# 304_usb_serial020000.net
KiCad netlist of a schematic drawn in EAGLE
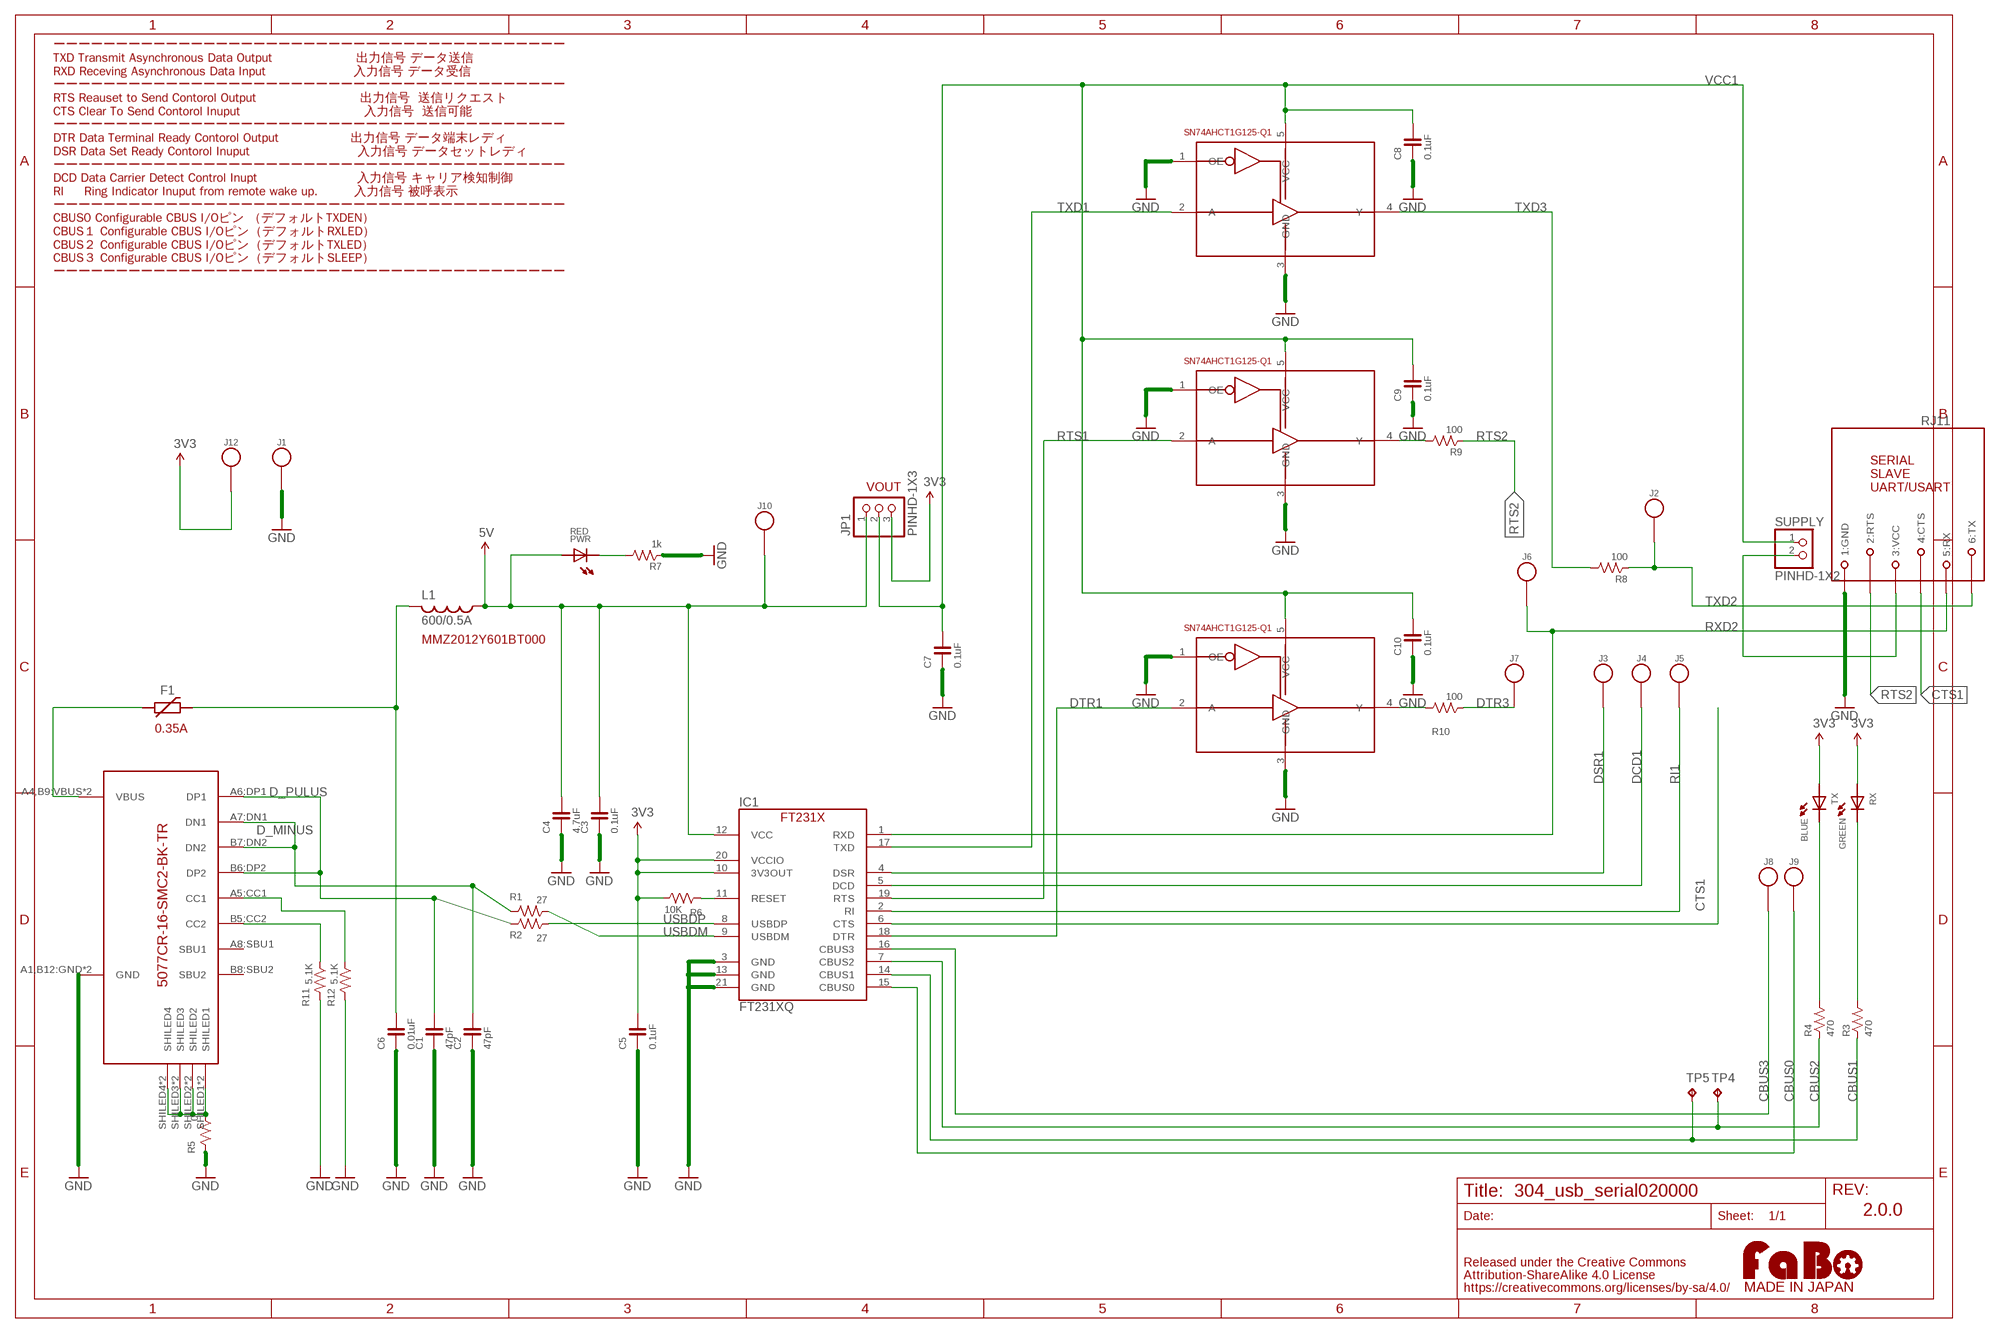
[diagram p0: schematic, sheet 1]

(export (version "E")
  (design (tool "Eeschema 10.0.6"))
  (components
    (comp (ref "C1")
      (value "47pF")
      (footprint "eagle-import:0603-NARROW")
      (libsource (lib "eagle-import") (part "CAPACITOR-0603_NARROW"))
    )
    (comp (ref "C2")
      (value "47pF")
      (footprint "eagle-import:0603-NARROW")
      (libsource (lib "eagle-import") (part "CAPACITOR-0603_NARROW"))
    )
    (comp (ref "C3")
      (value "0.1uF")
      (footprint "eagle-import:0603-NARROW")
      (libsource (lib "eagle-import") (part "CAPACITOR-0603_NARROW"))
    )
    (comp (ref "C4")
      (value "4.7uF")
      (footprint "eagle-import:0603-NARROW")
      (libsource (lib "eagle-import") (part "CAPACITOR-0603_NARROW"))
    )
    (comp (ref "C5")
      (value "0.1uF")
      (footprint "eagle-import:0603-NARROW")
      (libsource (lib "eagle-import") (part "CAPACITOR-0603_NARROW"))
    )
    (comp (ref "C6")
      (value "0.01uF")
      (footprint "eagle-import:0603-NARROW")
      (libsource (lib "eagle-import") (part "CAPACITOR-0603_NARROW"))
    )
    (comp (ref "C7")
      (value "0.1uF")
      (footprint "eagle-import:0603-NARROW")
      (libsource (lib "eagle-import") (part "CAPACITOR-0603_NARROW"))
    )
    (comp (ref "C8")
      (value "0.1uF")
      (footprint "eagle-import:0402-NO_SILK")
      (libsource (lib "eagle-import") (part "CAPACITOR-0402-NO_SILK"))
    )
    (comp (ref "C9")
      (value "0.1uF")
      (footprint "eagle-import:0402-NO_SILK")
      (libsource (lib "eagle-import") (part "CAPACITOR-0402-NO_SILK"))
    )
    (comp (ref "C10")
      (value "0.1uF")
      (footprint "eagle-import:0402-NO_SILK")
      (libsource (lib "eagle-import") (part "CAPACITOR-0402-NO_SILK"))
    )
    (comp (ref "F1")
      (value "350mA")
      (footprint "eagle-import:NANOSMDC035F")
      (libsource (lib "eagle-import") (part "POLYSWITCH"))
    )
    (comp (ref "IC1")
      (value "FT231XQ")
      (footprint "eagle-import:QFN-20_FT231X")
      (libsource (lib "eagle-import") (part "FT231XQ"))
    )
    (comp (ref "J1")
      (value "PIN_HEADER_1X1_NOLABEL_C")
      (footprint "eagle-import:PIN_1X1_NOLABEL")
      (libsource (lib "eagle-import") (part "PIN_HEADER_1X1_NOLABEL_C"))
    )
    (comp (ref "J2")
      (value "PIN_HEADER_1X1_NOLABEL_C")
      (footprint "eagle-import:PIN_1X1_NOLABEL")
      (libsource (lib "eagle-import") (part "PIN_HEADER_1X1_NOLABEL_C"))
    )
    (comp (ref "J3")
      (value "PIN_HEADER_1X1_NOLABEL_C")
      (footprint "eagle-import:PIN_1X1_NOLABEL")
      (libsource (lib "eagle-import") (part "PIN_HEADER_1X1_NOLABEL_C"))
    )
    (comp (ref "J4")
      (value "PIN_HEADER_1X1_NOLABEL_C")
      (footprint "eagle-import:PIN_1X1_NOLABEL")
      (libsource (lib "eagle-import") (part "PIN_HEADER_1X1_NOLABEL_C"))
    )
    (comp (ref "J5")
      (value "PIN_HEADER_1X1_NOLABEL_C")
      (footprint "eagle-import:PIN_1X1_NOLABEL")
      (libsource (lib "eagle-import") (part "PIN_HEADER_1X1_NOLABEL_C"))
    )
    (comp (ref "J6")
      (value "PIN_HEADER_1X1_NOLABEL_C")
      (footprint "eagle-import:PIN_1X1_NOLABEL")
      (libsource (lib "eagle-import") (part "PIN_HEADER_1X1_NOLABEL_C"))
    )
    (comp (ref "J7")
      (value "PIN_HEADER_1X1_NOLABEL_C")
      (footprint "eagle-import:PIN_1X1_NOLABEL")
      (libsource (lib "eagle-import") (part "PIN_HEADER_1X1_NOLABEL_C"))
    )
    (comp (ref "J8")
      (value "PIN_HEADER_1X1_NOLABEL_C")
      (footprint "eagle-import:PIN_1X1_NOLABEL")
      (libsource (lib "eagle-import") (part "PIN_HEADER_1X1_NOLABEL_C"))
    )
    (comp (ref "J9")
      (value "PIN_HEADER_1X1_NOLABEL_C")
      (footprint "eagle-import:PIN_1X1_NOLABEL")
      (libsource (lib "eagle-import") (part "PIN_HEADER_1X1_NOLABEL_C"))
    )
    (comp (ref "J10")
      (value "PIN_HEADER_1X1_NOLABEL_C")
      (footprint "eagle-import:PIN_1X1_NOLABEL")
      (libsource (lib "eagle-import") (part "PIN_HEADER_1X1_NOLABEL_C"))
    )
    (comp (ref "J12")
      (value "PIN_HEADER_1X1_NOLABEL_C")
      (footprint "eagle-import:PIN_1X1_NOLABEL")
      (libsource (lib "eagle-import") (part "PIN_HEADER_1X1_NOLABEL_C"))
    )
    (comp (ref "JP1")
      (value "PINHD-1X3")
      (footprint "eagle-import:1X03")
      (libsource (lib "eagle-import") (part "PINHD-1X3"))
    )
    (comp (ref "L1")
      (value "600/0.5A")
      (footprint "eagle-import:RESC0805_L")
      (libsource (lib "eagle-import") (part "INDUCTOR_0805_L"))
    )
    (comp (ref "PWR")
      (value "RED")
      (footprint "eagle-import:0603-NARROW")
      (libsource (lib "eagle-import") (part "LED-0603-NARROW"))
    )
    (comp (ref "R1")
      (value "27")
      (footprint "eagle-import:0603-NARROW")
      (libsource (lib "eagle-import") (part "RESISTOR-0603-NARROW"))
    )
    (comp (ref "R2")
      (value "27")
      (footprint "eagle-import:0603-NARROW")
      (libsource (lib "eagle-import") (part "RESISTOR-0603-NARROW"))
    )
    (comp (ref "R3")
      (value "470")
      (footprint "eagle-import:0603-NARROW")
      (libsource (lib "eagle-import") (part "RESISTOR-0603-NARROW"))
    )
    (comp (ref "R4")
      (value "470")
      (footprint "eagle-import:0603-NARROW")
      (libsource (lib "eagle-import") (part "RESISTOR-0603-NARROW"))
    )
    (comp (ref "R5")
      (value "0")
      (footprint "eagle-import:0603-NARROW")
      (libsource (lib "eagle-import") (part "RESISTOR-0603-NARROW"))
    )
    (comp (ref "R6")
      (value "10K")
      (footprint "eagle-import:0603-NARROW")
      (libsource (lib "eagle-import") (part "RESISTOR-0603-NARROW"))
    )
    (comp (ref "R7")
      (value "1k")
      (footprint "eagle-import:0603-NARROW")
      (libsource (lib "eagle-import") (part "RESISTOR-0603-NARROW"))
    )
    (comp (ref "R8")
      (value "100")
      (footprint "eagle-import:0603-NARROW")
      (libsource (lib "eagle-import") (part "RESISTOR-0603-NARROW"))
    )
    (comp (ref "R9")
      (value "100")
      (footprint "eagle-import:0603-NARROW")
      (libsource (lib "eagle-import") (part "RESISTOR-0603-NARROW"))
    )
    (comp (ref "R10")
      (value "100")
      (footprint "eagle-import:0603-NARROW")
      (libsource (lib "eagle-import") (part "RESISTOR-0603-NARROW"))
    )
    (comp (ref "R11")
      (value "5.1K")
      (footprint "eagle-import:0603-NARROW")
      (libsource (lib "eagle-import") (part "RESISTOR-0603-NARROW"))
    )
    (comp (ref "R12")
      (value "5.1K")
      (footprint "eagle-import:0603-NARROW")
      (libsource (lib "eagle-import") (part "RESISTOR-0603-NARROW"))
    )
    (comp (ref "RJ11")
      (value "MODULAR-JACK-6P-RJ11_SERIAL_S_USART")
      (footprint "eagle-import:7002-6PXC-X")
      (libsource (lib "eagle-import") (part "MODULAR-JACK-6P-RJ11_SERIAL_S_USART"))
    )
    (comp (ref "RX")
      (value "GREEN")
      (footprint "eagle-import:0603-NARROW")
      (libsource (lib "eagle-import") (part "LED-0603-NARROW"))
    )
    (comp (ref "SUPPLY")
      (value "PINHD-1X2")
      (footprint "eagle-import:1X02")
      (libsource (lib "eagle-import") (part "PINHD-1X2"))
    )
    (comp (ref "TP4")
      (value "TPB0,65")
      (footprint "eagle-import:B0,65")
      (libsource (lib "eagle-import") (part "TPB0,65"))
    )
    (comp (ref "TP5")
      (value "TPB0,65")
      (footprint "eagle-import:B0,65")
      (libsource (lib "eagle-import") (part "TPB0,65"))
    )
    (comp (ref "TX")
      (value "BLUE")
      (footprint "eagle-import:0603-NARROW")
      (libsource (lib "eagle-import") (part "LED-0603-NARROW"))
    )
    (comp (ref "U$2")
      (value "LOGO_FABO-M_BOTTOM")
      (footprint "eagle-import:LOGO_FABO_MS_BOTTOM")
      (libsource (lib "eagle-import") (part "LOGO_FABO-M_BOTTOM"))
    )
    (comp (ref "U$4")
      (value "5077CR-16-SMC2-BK-TR")
      (footprint "eagle-import:5077CR-16-SMC2-BK-TR")
      (libsource (lib "eagle-import") (part "5077CR-16-SMC2-BK-TR"))
    )
    (comp (ref "U$6")
      (value "SN74AHCT1G125-Q1")
      (footprint "eagle-import:SC70")
      (libsource (lib "eagle-import") (part "SN74AHCT1G125-Q1"))
    )
    (comp (ref "U$7")
      (value "SN74AHCT1G125-Q1")
      (footprint "eagle-import:SC70")
      (libsource (lib "eagle-import") (part "SN74AHCT1G125-Q1"))
    )
    (comp (ref "U$8")
      (value "SN74AHCT1G125-Q1")
      (footprint "eagle-import:SC70")
      (libsource (lib "eagle-import") (part "SN74AHCT1G125-Q1"))
    )
  )
  (nets
    (net (code "1") (name "/CBUS0") (class "Default")
      (node (ref "IC1") (pin "15") (pinfunction "CBUS0_15") (pintype "bidirectional"))
      (node (ref "J9") (pin "1") (pinfunction "1_1") (pintype "bidirectional"))
    )
    (net (code "2") (name "/CBUS1") (class "Default")
      (node (ref "IC1") (pin "14") (pinfunction "CBUS1_14") (pintype "bidirectional"))
      (node (ref "R3") (pin "1") (pinfunction "1_1") (pintype "bidirectional"))
      (node (ref "TP5") (pin "TP") (pinfunction "TP_TP") (pintype "input"))
    )
    (net (code "3") (name "/CBUS2") (class "Default")
      (node (ref "IC1") (pin "7") (pinfunction "CBUS2_7") (pintype "bidirectional"))
      (node (ref "R4") (pin "1") (pinfunction "1_1") (pintype "bidirectional"))
      (node (ref "TP4") (pin "TP") (pinfunction "TP_TP") (pintype "input"))
    )
    (net (code "4") (name "/CBUS3") (class "Default")
      (node (ref "IC1") (pin "16") (pinfunction "CBUS3_16") (pintype "bidirectional"))
      (node (ref "J8") (pin "1") (pinfunction "1_1") (pintype "bidirectional"))
    )
    (net (code "5") (name "/DCD1") (class "Default")
      (node (ref "IC1") (pin "5") (pinfunction "DCD_5") (pintype "bidirectional"))
      (node (ref "J4") (pin "1") (pinfunction "1_1") (pintype "bidirectional"))
    )
    (net (code "6") (name "/DSR1") (class "Default")
      (node (ref "IC1") (pin "4") (pinfunction "DSR_4") (pintype "bidirectional"))
      (node (ref "J3") (pin "1") (pinfunction "1_1") (pintype "bidirectional"))
    )
    (net (code "7") (name "/DTR1") (class "Default")
      (node (ref "IC1") (pin "18") (pinfunction "DTR_18") (pintype "bidirectional"))
      (node (ref "U$8") (pin "2") (pinfunction "A_2") (pintype "bidirectional"))
    )
    (net (code "8") (name "/DTR3") (class "Default")
      (node (ref "J7") (pin "1") (pinfunction "1_1") (pintype "bidirectional"))
      (node (ref "R10") (pin "1") (pinfunction "1_1") (pintype "bidirectional"))
    )
    (net (code "9") (name "/D_MINUS") (class "Default")
      (node (ref "C2") (pin "2") (pinfunction "2_2") (pintype "passive"))
      (node (ref "R1") (pin "2") (pinfunction "2_2") (pintype "bidirectional"))
      (node (ref "U$4") (pin "A7:DN1") (pinfunction "DN1_A7:DN1") (pintype "bidirectional"))
      (node (ref "U$4") (pin "B7:DN2") (pinfunction "DN2_B7:DN2") (pintype "bidirectional"))
    )
    (net (code "10") (name "/D_PULUS") (class "Default")
      (node (ref "C1") (pin "2") (pinfunction "2_2") (pintype "passive"))
      (node (ref "R2") (pin "2") (pinfunction "2_2") (pintype "bidirectional"))
      (node (ref "U$4") (pin "A6:DP1") (pinfunction "DP1_A6:DP1") (pintype "bidirectional"))
      (node (ref "U$4") (pin "B6:DP2") (pinfunction "DP2_B6:DP2") (pintype "bidirectional"))
    )
    (net (code "11") (name "/RI1") (class "Default")
      (node (ref "IC1") (pin "2") (pinfunction "RI_2") (pintype "bidirectional"))
      (node (ref "J5") (pin "1") (pinfunction "1_1") (pintype "bidirectional"))
    )
    (net (code "12") (name "/RTS1") (class "Default")
      (node (ref "IC1") (pin "19") (pinfunction "RTS_19") (pintype "bidirectional"))
      (node (ref "U$7") (pin "2") (pinfunction "A_2") (pintype "bidirectional"))
    )
    (net (code "13") (name "/RXD2") (class "Default")
      (node (ref "IC1") (pin "1") (pinfunction "RXD_1") (pintype "bidirectional"))
      (node (ref "J6") (pin "1") (pinfunction "1_1") (pintype "bidirectional"))
      (node (ref "RJ11") (pin "5") (pinfunction "5:RX_5") (pintype "output"))
    )
    (net (code "14") (name "/TXD1") (class "Default")
      (node (ref "IC1") (pin "17") (pinfunction "TXD_17") (pintype "bidirectional"))
      (node (ref "U$6") (pin "2") (pinfunction "A_2") (pintype "bidirectional"))
    )
    (net (code "15") (name "/TXD2") (class "Default")
      (node (ref "J2") (pin "1") (pinfunction "1_1") (pintype "bidirectional"))
      (node (ref "R8") (pin "1") (pinfunction "1_1") (pintype "bidirectional"))
      (node (ref "RJ11") (pin "6") (pinfunction "6:TX_6") (pintype "input"))
    )
    (net (code "16") (name "/TXD3") (class "Default")
      (node (ref "R8") (pin "2") (pinfunction "2_2") (pintype "bidirectional"))
      (node (ref "U$6") (pin "4") (pinfunction "Y_4") (pintype "bidirectional"))
    )
    (net (code "17") (name "/USBDM") (class "Default")
      (node (ref "IC1") (pin "9") (pinfunction "USBDM_9") (pintype "bidirectional"))
      (node (ref "R1") (pin "1") (pinfunction "1_1") (pintype "bidirectional"))
    )
    (net (code "18") (name "/USBDP") (class "Default")
      (node (ref "IC1") (pin "8") (pinfunction "USBDP_8") (pintype "bidirectional"))
      (node (ref "R2") (pin "1") (pinfunction "1_1") (pintype "bidirectional"))
    )
    (net (code "19") (name "/VCC1") (class "Default")
      (node (ref "C10") (pin "2") (pinfunction "2_2") (pintype "passive"))
      (node (ref "C7") (pin "2") (pinfunction "2_2") (pintype "passive"))
      (node (ref "C8") (pin "2") (pinfunction "2_2") (pintype "passive"))
      (node (ref "C9") (pin "2") (pinfunction "2_2") (pintype "passive"))
      (node (ref "JP1") (pin "2") (pinfunction "2_2") (pintype "passive"))
      (node (ref "SUPPLY") (pin "1") (pinfunction "1_1") (pintype "passive"))
      (node (ref "U$6") (pin "5") (pinfunction "VCC_5") (pintype "bidirectional"))
      (node (ref "U$7") (pin "5") (pinfunction "VCC_5") (pintype "bidirectional"))
      (node (ref "U$8") (pin "5") (pinfunction "VCC_5") (pintype "bidirectional"))
    )
    (net (code "20") (name "3V3") (class "Default")
      (node (ref "C5") (pin "2") (pinfunction "2_2") (pintype "passive"))
      (node (ref "IC1") (pin "10") (pinfunction "3V3OUT_10") (pintype "bidirectional"))
      (node (ref "IC1") (pin "20") (pinfunction "VCCIO_20") (pintype "bidirectional"))
      (node (ref "J12") (pin "1") (pinfunction "1_1") (pintype "bidirectional"))
      (node (ref "JP1") (pin "3") (pinfunction "3_3") (pintype "passive"))
      (node (ref "R6") (pin "1") (pinfunction "1_1") (pintype "bidirectional"))
      (node (ref "RX") (pin "ANODE") (pinfunction "ANODE_ANODE") (pintype "passive"))
      (node (ref "TX") (pin "ANODE") (pinfunction "ANODE_ANODE") (pintype "passive"))
    )
    (net (code "21") (name "5V") (class "Default")
      (node (ref "C3") (pin "2") (pinfunction "2_2") (pintype "passive"))
      (node (ref "C4") (pin "2") (pinfunction "2_2") (pintype "passive"))
      (node (ref "IC1") (pin "12") (pinfunction "VCC_12") (pintype "bidirectional"))
      (node (ref "J10") (pin "1") (pinfunction "1_1") (pintype "bidirectional"))
      (node (ref "JP1") (pin "1") (pinfunction "1_1") (pintype "passive"))
      (node (ref "L1") (pin "1") (pinfunction "1_1") (pintype "passive"))
      (node (ref "PWR") (pin "ANODE") (pinfunction "ANODE_ANODE") (pintype "passive"))
    )
    (net (code "22") (name "CTS1") (class "Default")
      (node (ref "IC1") (pin "6") (pinfunction "CTS_6") (pintype "bidirectional"))
      (node (ref "RJ11") (pin "4") (pinfunction "4:CTS_4") (pintype "bidirectional"))
    )
    (net (code "23") (name "GND") (class "Default")
      (node (ref "C1") (pin "1") (pinfunction "1_1") (pintype "passive"))
      (node (ref "C10") (pin "1") (pinfunction "1_1") (pintype "passive"))
      (node (ref "C2") (pin "1") (pinfunction "1_1") (pintype "passive"))
      (node (ref "C3") (pin "1") (pinfunction "1_1") (pintype "passive"))
      (node (ref "C4") (pin "1") (pinfunction "1_1") (pintype "passive"))
      (node (ref "C5") (pin "1") (pinfunction "1_1") (pintype "passive"))
      (node (ref "C6") (pin "1") (pinfunction "1_1") (pintype "passive"))
      (node (ref "C7") (pin "1") (pinfunction "1_1") (pintype "passive"))
      (node (ref "C8") (pin "1") (pinfunction "1_1") (pintype "passive"))
      (node (ref "C9") (pin "1") (pinfunction "1_1") (pintype "passive"))
      (node (ref "IC1") (pin "13") (pinfunction "GND_13") (pintype "bidirectional"))
      (node (ref "IC1") (pin "21") (pinfunction "GND_21") (pintype "bidirectional"))
      (node (ref "IC1") (pin "3") (pinfunction "GND_3") (pintype "bidirectional"))
      (node (ref "J1") (pin "1") (pinfunction "1_1") (pintype "bidirectional"))
      (node (ref "R11") (pin "2") (pinfunction "2_2") (pintype "bidirectional"))
      (node (ref "R12") (pin "2") (pinfunction "2_2") (pintype "bidirectional"))
      (node (ref "R5") (pin "2") (pinfunction "2_2") (pintype "bidirectional"))
      (node (ref "R7") (pin "1") (pinfunction "1_1") (pintype "bidirectional"))
      (node (ref "RJ11") (pin "1") (pinfunction "1:GND_1") (pintype "power_in"))
      (node (ref "U$4") (pin "A1,B12:GND") (pinfunction "GND_A1,B12:GND") (pintype "power_in"))
      (node (ref "U$4") (pin "B1,A12:GND") (pinfunction "GND_B1,A12:GND") (pintype "power_in"))
      (node (ref "U$6") (pin "1") (pinfunction "OE_1") (pintype "bidirectional"))
      (node (ref "U$6") (pin "3") (pinfunction "GND_3") (pintype "bidirectional"))
      (node (ref "U$7") (pin "1") (pinfunction "OE_1") (pintype "bidirectional"))
      (node (ref "U$7") (pin "3") (pinfunction "GND_3") (pintype "bidirectional"))
      (node (ref "U$8") (pin "1") (pinfunction "OE_1") (pintype "bidirectional"))
      (node (ref "U$8") (pin "3") (pinfunction "GND_3") (pintype "bidirectional"))
    )
    (net (code "24") (name "Net-(C6-Pad2)") (class "Default")
      (node (ref "C6") (pin "2") (pinfunction "2_2") (pintype "passive"))
      (node (ref "F1") (pin "2") (pinfunction "2_2") (pintype "bidirectional"))
      (node (ref "L1") (pin "2") (pinfunction "2_2") (pintype "passive"))
    )
    (net (code "25") (name "Net-(F1-Pad1)") (class "Default")
      (node (ref "F1") (pin "1") (pinfunction "1_1") (pintype "bidirectional"))
      (node (ref "U$4") (pin "A4,B9:VBUS") (pinfunction "VBUS_A4,B9:VBUS") (pintype "power_in"))
      (node (ref "U$4") (pin "B4,A9:VBUS") (pinfunction "VBUS_B4,A9:VBUS") (pintype "power_in"))
    )
    (net (code "26") (name "Net-(IC1-RESET)") (class "Default")
      (node (ref "IC1") (pin "11") (pinfunction "RESET_11") (pintype "bidirectional"))
      (node (ref "R6") (pin "2") (pinfunction "2_2") (pintype "bidirectional"))
    )
    (net (code "27") (name "Net-(PWR-PadCATHODE)") (class "Default")
      (node (ref "PWR") (pin "CATHODE") (pinfunction "CATHODE_CATHODE") (pintype "passive"))
      (node (ref "R7") (pin "2") (pinfunction "2_2") (pintype "bidirectional"))
    )
    (net (code "28") (name "Net-(R3-Pad2)") (class "Default")
      (node (ref "R3") (pin "2") (pinfunction "2_2") (pintype "bidirectional"))
      (node (ref "RX") (pin "CATHODE") (pinfunction "CATHODE_CATHODE") (pintype "passive"))
    )
    (net (code "29") (name "Net-(R4-Pad2)") (class "Default")
      (node (ref "R4") (pin "2") (pinfunction "2_2") (pintype "bidirectional"))
      (node (ref "TX") (pin "CATHODE") (pinfunction "CATHODE_CATHODE") (pintype "passive"))
    )
    (net (code "30") (name "Net-(R5-Pad1)") (class "Default")
      (node (ref "R5") (pin "1") (pinfunction "1_1") (pintype "bidirectional"))
      (node (ref "U$4") (pin "SHILED1") (pinfunction "SHILED1_SHILED1") (pintype "bidirectional"))
      (node (ref "U$4") (pin "SHILED2") (pinfunction "SHILED2_SHILED2") (pintype "bidirectional"))
      (node (ref "U$4") (pin "SHILED3") (pinfunction "SHILED3_SHILED3") (pintype "bidirectional"))
      (node (ref "U$4") (pin "SHILED4") (pinfunction "SHILED4_SHILED4") (pintype "bidirectional"))
      (node (ref "U$4") (pin "SHILED5") (pinfunction "SHILED1_SHILED5") (pintype "bidirectional"))
      (node (ref "U$4") (pin "SHILED6") (pinfunction "SHILED2_SHILED6") (pintype "bidirectional"))
      (node (ref "U$4") (pin "SHILED7") (pinfunction "SHILED3_SHILED7") (pintype "bidirectional"))
      (node (ref "U$4") (pin "SHILED8") (pinfunction "SHILED4_SHILED8") (pintype "bidirectional"))
    )
    (net (code "31") (name "Net-(RJ11-3:VCC)") (class "Default")
      (node (ref "RJ11") (pin "3") (pinfunction "3:VCC_3") (pintype "power_in"))
      (node (ref "SUPPLY") (pin "2") (pinfunction "2_2") (pintype "passive"))
    )
    (net (code "32") (name "Net-(U$4-CC1)") (class "Default")
      (node (ref "R12") (pin "1") (pinfunction "1_1") (pintype "bidirectional"))
      (node (ref "U$4") (pin "A5:CC1") (pinfunction "CC1_A5:CC1") (pintype "bidirectional"))
    )
    (net (code "33") (name "Net-(U$4-CC2)") (class "Default")
      (node (ref "R11") (pin "1") (pinfunction "1_1") (pintype "bidirectional"))
      (node (ref "U$4") (pin "B5:CC2") (pinfunction "CC2_B5:CC2") (pintype "bidirectional"))
    )
    (net (code "34") (name "Net-(U$7-Y)") (class "Default")
      (node (ref "R9") (pin "2") (pinfunction "2_2") (pintype "bidirectional"))
      (node (ref "U$7") (pin "4") (pinfunction "Y_4") (pintype "bidirectional"))
    )
    (net (code "35") (name "Net-(U$8-Y)") (class "Default")
      (node (ref "R10") (pin "2") (pinfunction "2_2") (pintype "bidirectional"))
      (node (ref "U$8") (pin "4") (pinfunction "Y_4") (pintype "bidirectional"))
    )
    (net (code "36") (name "RTS2") (class "Default")
      (node (ref "R9") (pin "1") (pinfunction "1_1") (pintype "bidirectional"))
      (node (ref "RJ11") (pin "2") (pinfunction "2:RTS_2") (pintype "bidirectional"))
    )
    (net (code "37") (name "unconnected-(U$4-SBU1-PadA8:SBU1)") (class "Default")
      (node (ref "U$4") (pin "A8:SBU1") (pinfunction "SBU1_A8:SBU1") (pintype "bidirectional"))
    )
    (net (code "38") (name "unconnected-(U$4-SBU2-PadB8:SBU2)") (class "Default")
      (node (ref "U$4") (pin "B8:SBU2") (pinfunction "SBU2_B8:SBU2") (pintype "bidirectional"))
    )
  )
)
